# Motor_Drivers.net
KiCad netlist of a schematic drawn in Altium Designer
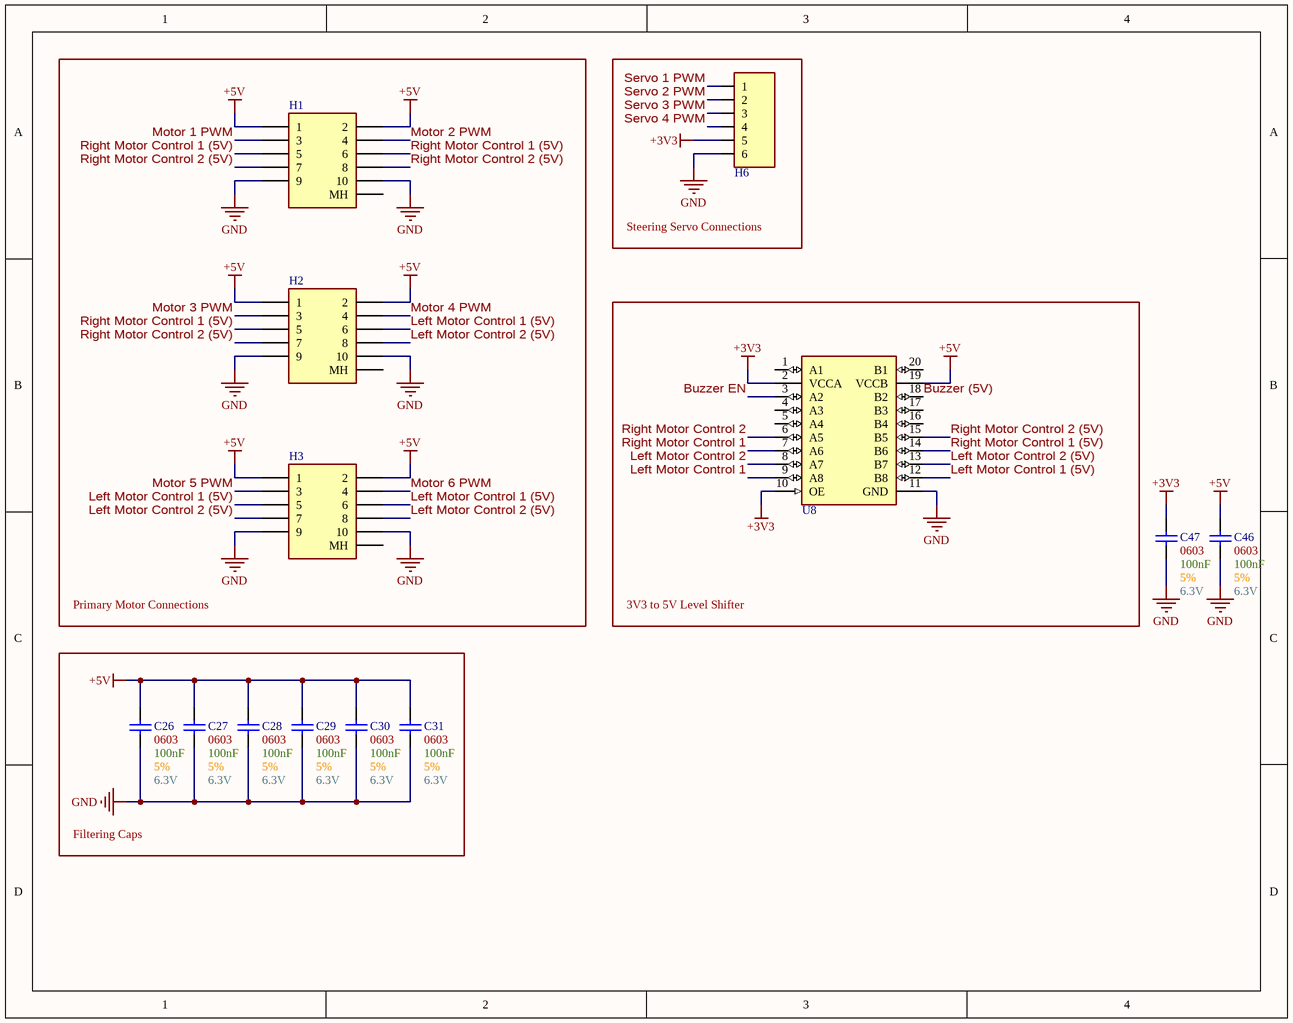
[diagram p0: Motor Drivers.SchDoc]

(export (version "E")
  (design (tool "Eeschema 10.0.6"))
  (components
    (comp (ref "C26")
      (value "[Cap] SMD Nonpolarized")
      (footprint "[Cap] SMD 0603")
      (fields
        (field (name "SIZE PACKAGE") "0603")
        (field (name "CAPACITANCE") "100nF")
        (field (name "VOLTAGE") "6.3V")
        (field (name "TOLERANCE") "5%")
      )
      (libsource (lib "RADM Components") (part "[Cap] SMD Nonpolarized"))
    )
    (comp (ref "C27")
      (value "[Cap] SMD Nonpolarized")
      (footprint "[Cap] SMD 0603")
      (fields
        (field (name "SIZE PACKAGE") "0603")
        (field (name "CAPACITANCE") "100nF")
        (field (name "VOLTAGE") "6.3V")
        (field (name "TOLERANCE") "5%")
      )
      (libsource (lib "RADM Components") (part "[Cap] SMD Nonpolarized"))
    )
    (comp (ref "C28")
      (value "[Cap] SMD Nonpolarized")
      (footprint "[Cap] SMD 0603")
      (fields
        (field (name "SIZE PACKAGE") "0603")
        (field (name "CAPACITANCE") "100nF")
        (field (name "VOLTAGE") "6.3V")
        (field (name "TOLERANCE") "5%")
      )
      (libsource (lib "RADM Components") (part "[Cap] SMD Nonpolarized"))
    )
    (comp (ref "C29")
      (value "[Cap] SMD Nonpolarized")
      (footprint "[Cap] SMD 0603")
      (fields
        (field (name "SIZE PACKAGE") "0603")
        (field (name "CAPACITANCE") "100nF")
        (field (name "VOLTAGE") "6.3V")
        (field (name "TOLERANCE") "5%")
      )
      (libsource (lib "RADM Components") (part "[Cap] SMD Nonpolarized"))
    )
    (comp (ref "C30")
      (value "[Cap] SMD Nonpolarized")
      (footprint "[Cap] SMD 0603")
      (fields
        (field (name "SIZE PACKAGE") "0603")
        (field (name "CAPACITANCE") "100nF")
        (field (name "VOLTAGE") "6.3V")
        (field (name "TOLERANCE") "5%")
      )
      (libsource (lib "RADM Components") (part "[Cap] SMD Nonpolarized"))
    )
    (comp (ref "C31")
      (value "[Cap] SMD Nonpolarized")
      (footprint "[Cap] SMD 0603")
      (fields
        (field (name "SIZE PACKAGE") "0603")
        (field (name "CAPACITANCE") "100nF")
        (field (name "VOLTAGE") "6.3V")
        (field (name "TOLERANCE") "5%")
      )
      (libsource (lib "RADM Components") (part "[Cap] SMD Nonpolarized"))
    )
    (comp (ref "C46")
      (value "[Cap] SMD Nonpolarized")
      (footprint "[Cap] SMD 0603")
      (fields
        (field (name "SIZE PACKAGE") "0603")
        (field (name "CAPACITANCE") "100nF")
        (field (name "VOLTAGE") "6.3V")
        (field (name "TOLERANCE") "5%")
      )
      (libsource (lib "RADM Components") (part "[Cap] SMD Nonpolarized"))
    )
    (comp (ref "C47")
      (value "[Cap] SMD Nonpolarized")
      (footprint "[Cap] SMD 0603")
      (fields
        (field (name "SIZE PACKAGE") "0603")
        (field (name "CAPACITANCE") "100nF")
        (field (name "VOLTAGE") "6.3V")
        (field (name "TOLERANCE") "5%")
      )
      (libsource (lib "RADM Components") (part "[Cap] SMD Nonpolarized"))
    )
    (comp (ref "H1")
      (value "[Header] Shrouded 2x5 SMD")
      (footprint "[Header] Shrouded 2x5 SMD")
      (libsource (lib "RADM Connectors") (part "[Header] Shrouded 2x5 SMD"))
    )
    (comp (ref "H2")
      (value "[Header] Shrouded 2x5 SMD")
      (footprint "[Header] Shrouded 2x5 SMD")
      (libsource (lib "RADM Connectors") (part "[Header] Shrouded 2x5 SMD"))
    )
    (comp (ref "H3")
      (value "[Header] Shrouded 2x5 SMD")
      (footprint "[Header] Shrouded 2x5 SMD")
      (libsource (lib "RADM Connectors") (part "[Header] Shrouded 2x5 SMD"))
    )
    (comp (ref "H6")
      (value "[Header] Shrouded 1x6 Male")
      (footprint "[Header] Shrouded 1x6 Male")
      (description "0705430005\r\nMates with 0050579406")
      (libsource (lib "RADM Connectors") (part "[Header] Shrouded 1x6 Male"))
    )
    (comp (ref "U8")
      (value "[IC] Level Shifter (2)")
      (footprint "[IC] Level Shifter (2)")
      (description "TXS0108EQPWRQ1")
      (libsource (lib "RADM Components") (part "[IC] Level Shifter (2)"))
    )
  )
  (nets
    (net (code "1") (name "+3V3") (class "Default")
      (node (ref "C47") (pin "2") (pinfunction "2_2") (pintype "passive"))
      (node (ref "H6") (pin "5") (pinfunction "5_5") (pintype "passive"))
      (node (ref "U8") (pin "10") (pinfunction "OE_10") (pintype "input"))
      (node (ref "U8") (pin "2") (pinfunction "VCCA_2") (pintype "power_in"))
    )
    (net (code "2") (name "+5V") (class "Default")
      (node (ref "C26") (pin "2") (pinfunction "2_2") (pintype "passive"))
      (node (ref "C27") (pin "2") (pinfunction "2_2") (pintype "passive"))
      (node (ref "C28") (pin "2") (pinfunction "2_2") (pintype "passive"))
      (node (ref "C29") (pin "2") (pinfunction "2_2") (pintype "passive"))
      (node (ref "C30") (pin "2") (pinfunction "2_2") (pintype "passive"))
      (node (ref "C31") (pin "2") (pinfunction "2_2") (pintype "passive"))
      (node (ref "C46") (pin "2") (pinfunction "2_2") (pintype "passive"))
      (node (ref "H1") (pin "1") (pinfunction "1_1") (pintype "passive"))
      (node (ref "H1") (pin "2") (pinfunction "2_2") (pintype "passive"))
      (node (ref "H2") (pin "1") (pinfunction "1_1") (pintype "passive"))
      (node (ref "H2") (pin "2") (pinfunction "2_2") (pintype "passive"))
      (node (ref "H3") (pin "1") (pinfunction "1_1") (pintype "passive"))
      (node (ref "H3") (pin "2") (pinfunction "2_2") (pintype "passive"))
      (node (ref "U8") (pin "19") (pinfunction "VCCB_19") (pintype "power_in"))
    )
    (net (code "3") (name "/Buzzer (5V)") (class "Default")
      (node (ref "U8") (pin "18") (pinfunction "B2_18") (pintype "bidirectional"))
    )
    (net (code "4") (name "/Buzzer EN") (class "Default")
      (node (ref "U8") (pin "3") (pinfunction "A2_3") (pintype "bidirectional"))
    )
    (net (code "5") (name "/Left Motor Control 1") (class "Default")
      (node (ref "U8") (pin "9") (pinfunction "A8_9") (pintype "bidirectional"))
    )
    (net (code "6") (name "/Left Motor Control 1 (5V)") (class "Default")
      (node (ref "H2") (pin "6") (pinfunction "6_6") (pintype "passive"))
      (node (ref "H3") (pin "5") (pinfunction "5_5") (pintype "passive"))
      (node (ref "H3") (pin "6") (pinfunction "6_6") (pintype "passive"))
      (node (ref "U8") (pin "12") (pinfunction "B8_12") (pintype "bidirectional"))
    )
    (net (code "7") (name "/Left Motor Control 2") (class "Default")
      (node (ref "U8") (pin "8") (pinfunction "A7_8") (pintype "bidirectional"))
    )
    (net (code "8") (name "/Left Motor Control 2 (5V)") (class "Default")
      (node (ref "H2") (pin "8") (pinfunction "8_8") (pintype "passive"))
      (node (ref "H3") (pin "7") (pinfunction "7_7") (pintype "passive"))
      (node (ref "H3") (pin "8") (pinfunction "8_8") (pintype "passive"))
      (node (ref "U8") (pin "13") (pinfunction "B7_13") (pintype "bidirectional"))
    )
    (net (code "9") (name "/Motor 1 PWM") (class "Default")
      (node (ref "H1") (pin "3") (pinfunction "3_3") (pintype "passive"))
    )
    (net (code "10") (name "/Motor 2 PWM") (class "Default")
      (node (ref "H1") (pin "4") (pinfunction "4_4") (pintype "passive"))
    )
    (net (code "11") (name "/Motor 3 PWM") (class "Default")
      (node (ref "H2") (pin "3") (pinfunction "3_3") (pintype "passive"))
    )
    (net (code "12") (name "/Motor 4 PWM") (class "Default")
      (node (ref "H2") (pin "4") (pinfunction "4_4") (pintype "passive"))
    )
    (net (code "13") (name "/Motor 5 PWM") (class "Default")
      (node (ref "H3") (pin "3") (pinfunction "3_3") (pintype "passive"))
    )
    (net (code "14") (name "/Motor 6 PWM") (class "Default")
      (node (ref "H3") (pin "4") (pinfunction "4_4") (pintype "passive"))
    )
    (net (code "15") (name "/Right Motor Control 1") (class "Default")
      (node (ref "U8") (pin "7") (pinfunction "A6_7") (pintype "bidirectional"))
    )
    (net (code "16") (name "/Right Motor Control 1 (5V)") (class "Default")
      (node (ref "H1") (pin "5") (pinfunction "5_5") (pintype "passive"))
      (node (ref "H1") (pin "6") (pinfunction "6_6") (pintype "passive"))
      (node (ref "H2") (pin "5") (pinfunction "5_5") (pintype "passive"))
      (node (ref "U8") (pin "14") (pinfunction "B6_14") (pintype "bidirectional"))
    )
    (net (code "17") (name "/Right Motor Control 2") (class "Default")
      (node (ref "U8") (pin "6") (pinfunction "A5_6") (pintype "bidirectional"))
    )
    (net (code "18") (name "/Right Motor Control 2 (5V)") (class "Default")
      (node (ref "H1") (pin "7") (pinfunction "7_7") (pintype "passive"))
      (node (ref "H1") (pin "8") (pinfunction "8_8") (pintype "passive"))
      (node (ref "H2") (pin "7") (pinfunction "7_7") (pintype "passive"))
      (node (ref "U8") (pin "15") (pinfunction "B5_15") (pintype "bidirectional"))
    )
    (net (code "19") (name "/Servo 1 PWM") (class "Default")
      (node (ref "H6") (pin "1") (pinfunction "1_1") (pintype "passive"))
    )
    (net (code "20") (name "/Servo 2 PWM") (class "Default")
      (node (ref "H6") (pin "2") (pinfunction "2_2") (pintype "passive"))
    )
    (net (code "21") (name "/Servo 3 PWM") (class "Default")
      (node (ref "H6") (pin "3") (pinfunction "3_3") (pintype "passive"))
    )
    (net (code "22") (name "/Servo 4 PWM") (class "Default")
      (node (ref "H6") (pin "4") (pinfunction "4_4") (pintype "passive"))
    )
    (net (code "23") (name "GND") (class "Default")
      (node (ref "C26") (pin "1") (pinfunction "1_1") (pintype "passive"))
      (node (ref "C27") (pin "1") (pinfunction "1_1") (pintype "passive"))
      (node (ref "C28") (pin "1") (pinfunction "1_1") (pintype "passive"))
      (node (ref "C29") (pin "1") (pinfunction "1_1") (pintype "passive"))
      (node (ref "C30") (pin "1") (pinfunction "1_1") (pintype "passive"))
      (node (ref "C31") (pin "1") (pinfunction "1_1") (pintype "passive"))
      (node (ref "C46") (pin "1") (pinfunction "1_1") (pintype "passive"))
      (node (ref "C47") (pin "1") (pinfunction "1_1") (pintype "passive"))
      (node (ref "H1") (pin "10") (pinfunction "10_10") (pintype "passive"))
      (node (ref "H1") (pin "9") (pinfunction "9_9") (pintype "passive"))
      (node (ref "H2") (pin "10") (pinfunction "10_10") (pintype "passive"))
      (node (ref "H2") (pin "9") (pinfunction "9_9") (pintype "passive"))
      (node (ref "H3") (pin "10") (pinfunction "10_10") (pintype "passive"))
      (node (ref "H3") (pin "9") (pinfunction "9_9") (pintype "passive"))
      (node (ref "H6") (pin "6") (pinfunction "6_6") (pintype "passive"))
      (node (ref "U8") (pin "11") (pinfunction "GND_11") (pintype "power_in"))
    )
    (net (code "24") (name "unconnected-(H1-MH-PadX)") (class "Default")
      (node (ref "H1") (pin "X") (pinfunction "MH_X") (pintype "passive"))
    )
    (net (code "25") (name "unconnected-(H2-MH-PadX)") (class "Default")
      (node (ref "H2") (pin "X") (pinfunction "MH_X") (pintype "passive"))
    )
    (net (code "26") (name "unconnected-(H3-MH-PadX)") (class "Default")
      (node (ref "H3") (pin "X") (pinfunction "MH_X") (pintype "passive"))
    )
    (net (code "27") (name "unconnected-(U8-A1-Pad1)") (class "Default")
      (node (ref "U8") (pin "1") (pinfunction "A1_1") (pintype "bidirectional"))
    )
    (net (code "28") (name "unconnected-(U8-A3-Pad4)") (class "Default")
      (node (ref "U8") (pin "4") (pinfunction "A3_4") (pintype "bidirectional"))
    )
    (net (code "29") (name "unconnected-(U8-A4-Pad5)") (class "Default")
      (node (ref "U8") (pin "5") (pinfunction "A4_5") (pintype "bidirectional"))
    )
    (net (code "30") (name "unconnected-(U8-B1-Pad20)") (class "Default")
      (node (ref "U8") (pin "20") (pinfunction "B1_20") (pintype "bidirectional"))
    )
    (net (code "31") (name "unconnected-(U8-B3-Pad17)") (class "Default")
      (node (ref "U8") (pin "17") (pinfunction "B3_17") (pintype "bidirectional"))
    )
    (net (code "32") (name "unconnected-(U8-B4-Pad16)") (class "Default")
      (node (ref "U8") (pin "16") (pinfunction "B4_16") (pintype "bidirectional"))
    )
  )
)
